# blinky_board.net
KiCad netlist of a schematic drawn in EAGLE
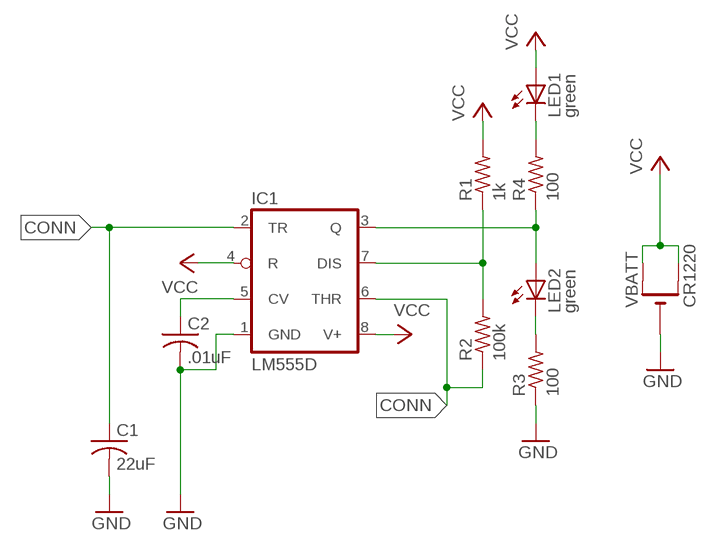
[diagram p0: schematic, sheet 1]

(export (version "E")
  (design (tool "Eeschema 10.0.6"))
  (components
    (comp (ref "C1")
      (value "22uF")
      (footprint "eagle-import:C0805")
      (libsource (lib "eagle-import") (part "C-USC0805"))
    )
    (comp (ref "C2")
      (value ".01uF")
      (footprint "eagle-import:C0805")
      (libsource (lib "eagle-import") (part "C-USC0805"))
    )
    (comp (ref "IC1")
      (value "LM555D")
      (footprint "eagle-import:SO08")
      (libsource (lib "eagle-import") (part "555DLM"))
    )
    (comp (ref "LED1")
      (value "green")
      (footprint "eagle-import:CHIPLED_0805")
      (libsource (lib "eagle-import") (part "LEDCHIPLED_0805"))
    )
    (comp (ref "LED2")
      (value "green")
      (footprint "eagle-import:CHIPLED_0805")
      (libsource (lib "eagle-import") (part "LEDCHIPLED_0805"))
    )
    (comp (ref "R1")
      (value "1k")
      (footprint "eagle-import:R0805")
      (libsource (lib "eagle-import") (part "R-US_R0805"))
    )
    (comp (ref "R2")
      (value "100k")
      (footprint "eagle-import:R0805")
      (libsource (lib "eagle-import") (part "R-US_R0805"))
    )
    (comp (ref "R3")
      (value "100")
      (footprint "eagle-import:R0805")
      (libsource (lib "eagle-import") (part "R-US_R0805"))
    )
    (comp (ref "R4")
      (value "100")
      (footprint "eagle-import:R0805")
      (libsource (lib "eagle-import") (part "R-US_R0805"))
    )
    (comp (ref "VBATT")
      (value "CR1220")
      (footprint "eagle-import:CR1220-SMD")
      (libsource (lib "eagle-import") (part "CR1220SMT"))
    )
  )
  (nets
    (net (code "1") (name "CONN") (class "Default")
      (node (ref "C1") (pin "1") (pinfunction "1_1") (pintype "passive"))
      (node (ref "IC1") (pin "2") (pinfunction "TR_2") (pintype "input"))
      (node (ref "IC1") (pin "6") (pinfunction "THR_6") (pintype "input"))
      (node (ref "R2") (pin "1") (pinfunction "1_1") (pintype "passive"))
    )
    (net (code "2") (name "GND") (class "Default")
      (node (ref "C1") (pin "2") (pinfunction "2_2") (pintype "passive"))
      (node (ref "C2") (pin "2") (pinfunction "2_2") (pintype "passive"))
      (node (ref "IC1") (pin "1") (pinfunction "GND_1") (pintype "power_in"))
      (node (ref "R3") (pin "1") (pinfunction "1_1") (pintype "passive"))
      (node (ref "VBATT") (pin "-") (pinfunction "-_-") (pintype "passive"))
    )
    (net (code "3") (name "Net-(IC1-CV)") (class "Default")
      (node (ref "C2") (pin "1") (pinfunction "1_1") (pintype "passive"))
      (node (ref "IC1") (pin "5") (pinfunction "CV_5") (pintype "input"))
    )
    (net (code "4") (name "Net-(IC1-DIS)") (class "Default")
      (node (ref "IC1") (pin "7") (pinfunction "DIS_7") (pintype "input"))
      (node (ref "R1") (pin "1") (pinfunction "1_1") (pintype "passive"))
      (node (ref "R2") (pin "2") (pinfunction "2_2") (pintype "passive"))
    )
    (net (code "5") (name "Net-(IC1-Q)") (class "Default")
      (node (ref "IC1") (pin "3") (pinfunction "Q_3") (pintype "output"))
      (node (ref "LED2") (pin "A") (pinfunction "A_A") (pintype "passive"))
      (node (ref "R4") (pin "1") (pinfunction "1_1") (pintype "passive"))
    )
    (net (code "6") (name "Net-(LED1-PadC)") (class "Default")
      (node (ref "LED1") (pin "C") (pinfunction "C_C") (pintype "passive"))
      (node (ref "R4") (pin "2") (pinfunction "2_2") (pintype "passive"))
    )
    (net (code "7") (name "Net-(LED2-PadC)") (class "Default")
      (node (ref "LED2") (pin "C") (pinfunction "C_C") (pintype "passive"))
      (node (ref "R3") (pin "2") (pinfunction "2_2") (pintype "passive"))
    )
    (net (code "8") (name "VCC") (class "Default")
      (node (ref "IC1") (pin "4") (pinfunction "R_4") (pintype "input"))
      (node (ref "IC1") (pin "8") (pinfunction "V+_8") (pintype "power_in"))
      (node (ref "LED1") (pin "A") (pinfunction "A_A") (pintype "passive"))
      (node (ref "R1") (pin "2") (pinfunction "2_2") (pintype "passive"))
      (node (ref "VBATT") (pin "+$1") (pinfunction "+_+$1") (pintype "passive"))
      (node (ref "VBATT") (pin "+$2") (pinfunction "+1_+$2") (pintype "passive"))
    )
  )
)
